# Clock_Extension.net
KiCad netlist of a schematic drawn in EAGLE
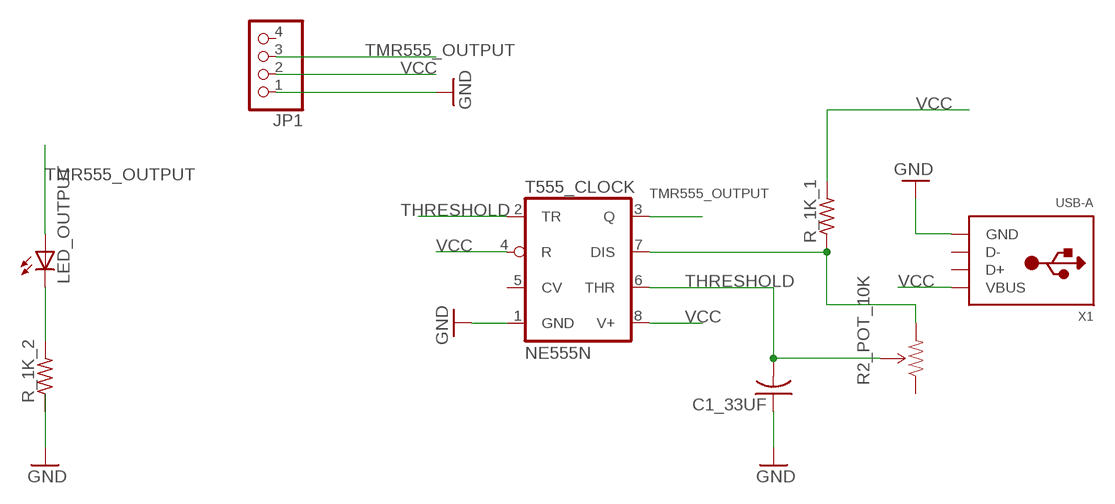
[diagram p0: schematic, sheet 1]

(export (version "E")
  (design (tool "Eeschema 10.0.6"))
  (components
    (comp (ref "C1_33UF")
      (value "C-US025-030X050")
      (footprint "eagle-import:C025-030X050")
      (libsource (lib "eagle-import") (part "C-US025-030X050"))
    )
    (comp (ref "JP1")
      (value "PINHD-1X4")
      (footprint "eagle-import:1X04")
      (libsource (lib "eagle-import") (part "PINHD-1X4"))
    )
    (comp (ref "LED_OUTPUT")
      (value "LEDSMT1206")
      (footprint "eagle-import:1206")
      (libsource (lib "eagle-import") (part "LEDSMT1206"))
    )
    (comp (ref "R2_POT_10K")
      (value "TRIMPOTPTH")
      (footprint "eagle-import:TRIM_POT_PTH")
      (libsource (lib "eagle-import") (part "TRIMPOTPTH"))
    )
    (comp (ref "R_1K_1")
      (value "R-US_R1206")
      (footprint "eagle-import:R1206")
      (libsource (lib "eagle-import") (part "R-US_R1206"))
    )
    (comp (ref "R_1K_2")
      (value "R-US_R1206")
      (footprint "eagle-import:R1206")
      (libsource (lib "eagle-import") (part "R-US_R1206"))
    )
    (comp (ref "T555_CLOCK")
      (value "NE555N")
      (footprint "eagle-import:DIL08")
      (libsource (lib "eagle-import") (part "555NNE"))
    )
    (comp (ref "X1")
      (value "USB-A")
      (footprint "eagle-import:MOLEX_480371000")
      (libsource (lib "eagle-import") (part "USB-A"))
    )
  )
  (nets
    (net (code "1") (name "/THRESHOLD") (class "Default")
      (node (ref "C1_33UF") (pin "2") (pinfunction "2_2") (pintype "passive"))
      (node (ref "R2_POT_10K") (pin "2") (pinfunction "WIPER_2") (pintype "passive"))
      (node (ref "T555_CLOCK") (pin "2") (pinfunction "TR_2") (pintype "input"))
      (node (ref "T555_CLOCK") (pin "6") (pinfunction "THR_6") (pintype "input"))
    )
    (net (code "2") (name "/TMR555_OUTPUT") (class "Default")
      (node (ref "JP1") (pin "3") (pinfunction "3_3") (pintype "passive"))
      (node (ref "LED_OUTPUT") (pin "A") (pinfunction "A_A") (pintype "passive"))
      (node (ref "T555_CLOCK") (pin "3") (pinfunction "Q_3") (pintype "output"))
    )
    (net (code "3") (name "/VCC") (class "Default")
      (node (ref "JP1") (pin "2") (pinfunction "2_2") (pintype "passive"))
      (node (ref "R_1K_1") (pin "2") (pinfunction "2_2") (pintype "passive"))
      (node (ref "T555_CLOCK") (pin "4") (pinfunction "R_4") (pintype "input"))
      (node (ref "T555_CLOCK") (pin "8") (pinfunction "V+_8") (pintype "power_in"))
      (node (ref "X1") (pin "1") (pinfunction "VBUS_1") (pintype "power_in"))
    )
    (net (code "4") (name "GND") (class "Default")
      (node (ref "C1_33UF") (pin "1") (pinfunction "1_1") (pintype "passive"))
      (node (ref "JP1") (pin "1") (pinfunction "1_1") (pintype "passive"))
      (node (ref "R_1K_2") (pin "1") (pinfunction "1_1") (pintype "passive"))
      (node (ref "T555_CLOCK") (pin "1") (pinfunction "GND_1") (pintype "power_in"))
      (node (ref "X1") (pin "4") (pinfunction "GND_4") (pintype "power_in"))
    )
    (net (code "5") (name "Net-(LED_OUTPUT-PadC)") (class "Default")
      (node (ref "LED_OUTPUT") (pin "C") (pinfunction "C_C") (pintype "passive"))
      (node (ref "R_1K_2") (pin "2") (pinfunction "2_2") (pintype "passive"))
    )
    (net (code "6") (name "Net-(R2_POT_10K-CW)") (class "Default")
      (node (ref "R2_POT_10K") (pin "3") (pinfunction "CW_3") (pintype "passive"))
      (node (ref "R_1K_1") (pin "1") (pinfunction "1_1") (pintype "passive"))
      (node (ref "T555_CLOCK") (pin "7") (pinfunction "DIS_7") (pintype "input"))
    )
    (net (code "7") (name "unconnected-(JP1-Pad4)") (class "Default")
      (node (ref "JP1") (pin "4") (pinfunction "4_4") (pintype "passive"))
    )
    (net (code "8") (name "unconnected-(R2_POT_10K-CCW-Pad1)") (class "Default")
      (node (ref "R2_POT_10K") (pin "1") (pinfunction "CCW_1") (pintype "passive"))
    )
    (net (code "9") (name "unconnected-(T555_CLOCK-CV-Pad5)") (class "Default")
      (node (ref "T555_CLOCK") (pin "5") (pinfunction "CV_5") (pintype "input"))
    )
    (net (code "10") (name "unconnected-(X1-D+-Pad3)") (class "Default")
      (node (ref "X1") (pin "3") (pinfunction "D+_3") (pintype "bidirectional"))
    )
    (net (code "11") (name "unconnected-(X1-D--Pad2)") (class "Default")
      (node (ref "X1") (pin "2") (pinfunction "D-_2") (pintype "bidirectional"))
    )
  )
)
